# RecoveryBoard.net
KiCad netlist of a schematic drawn in EAGLE
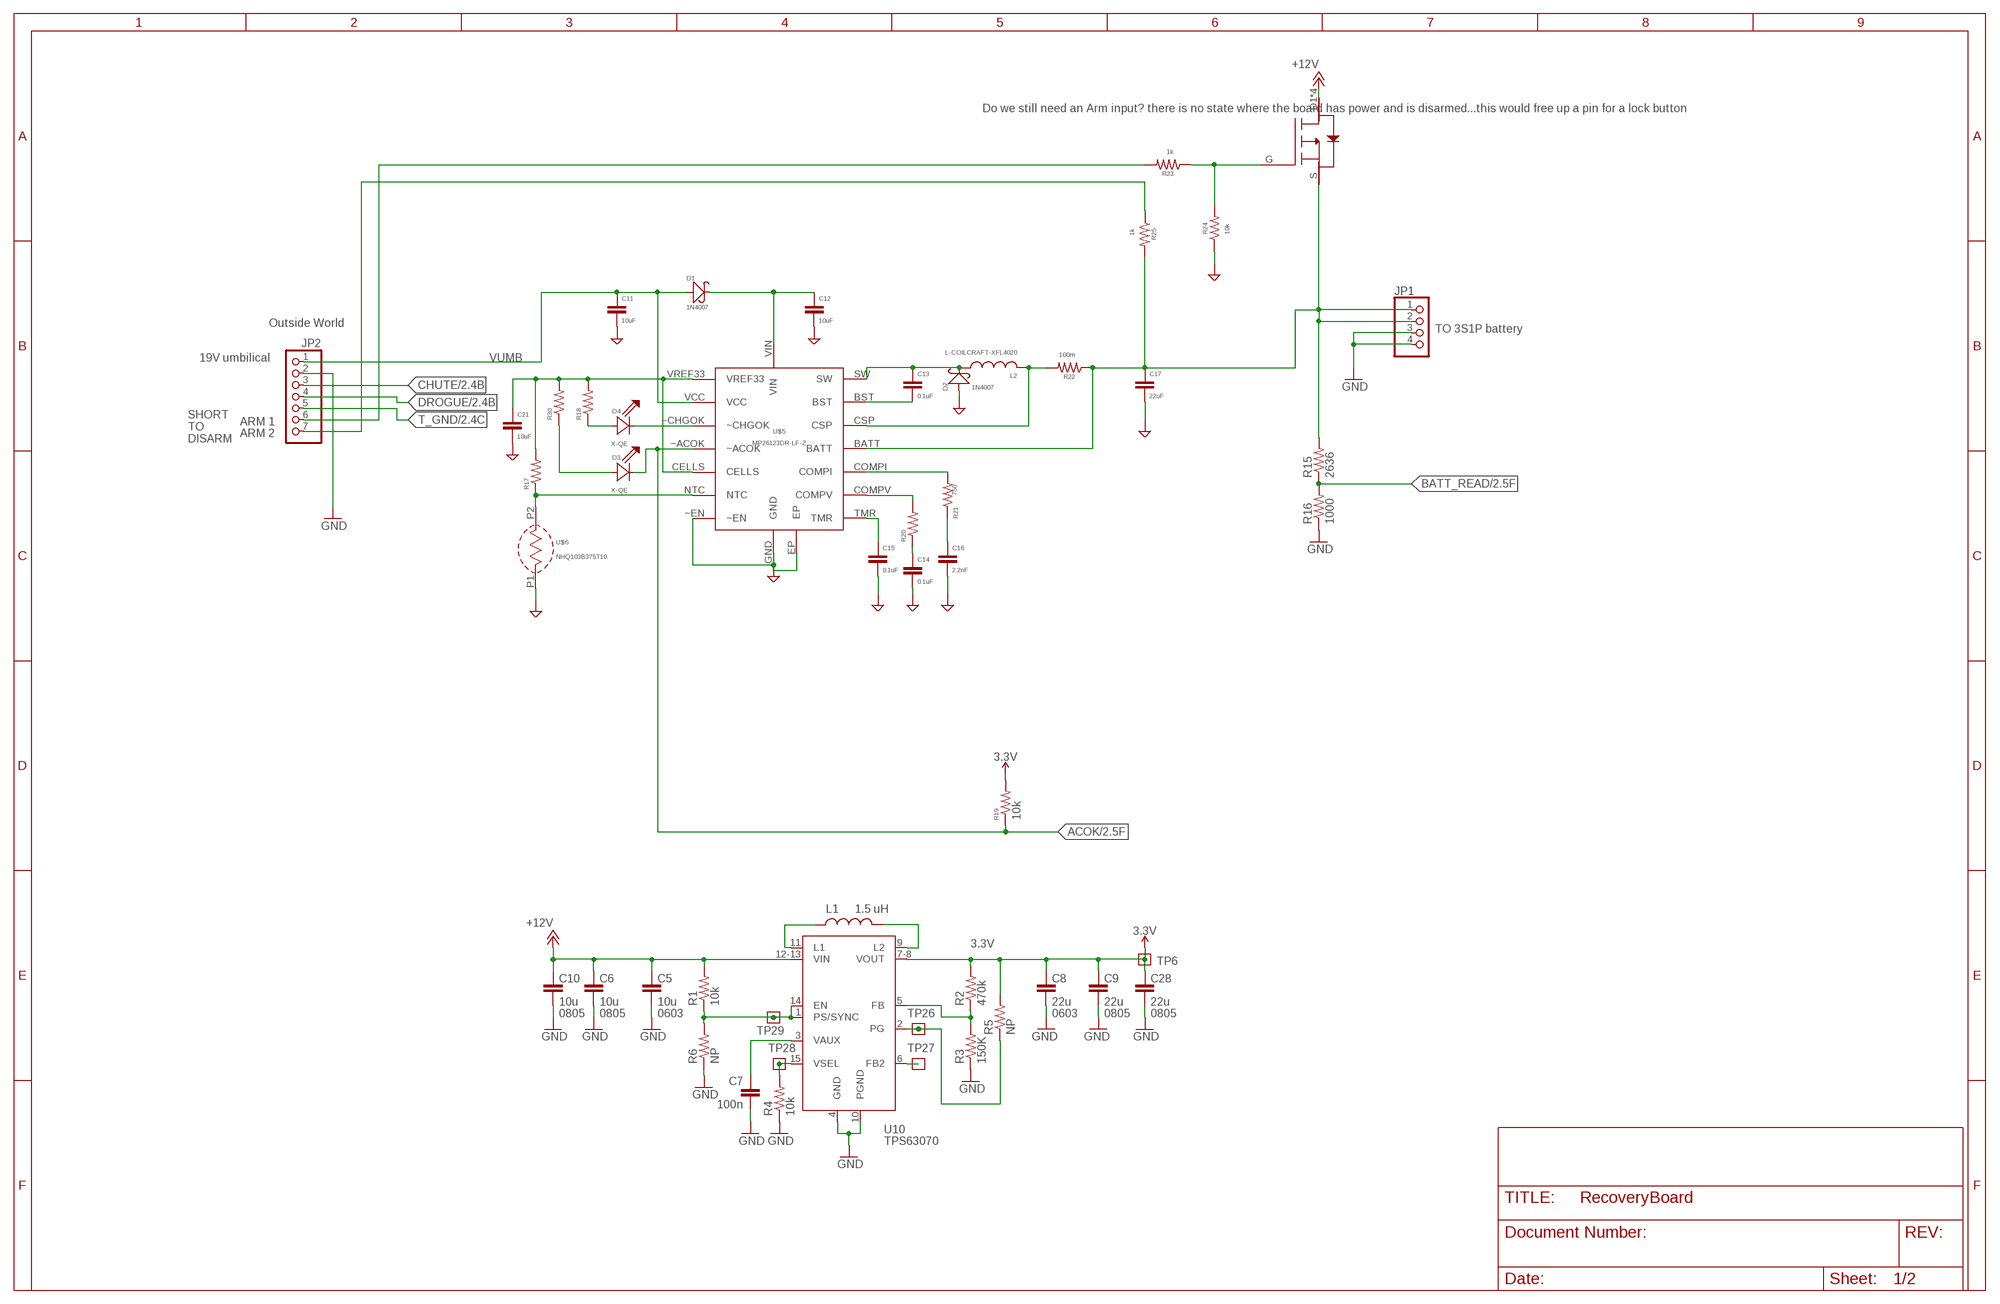
[diagram p0: schematic, sheet 1]
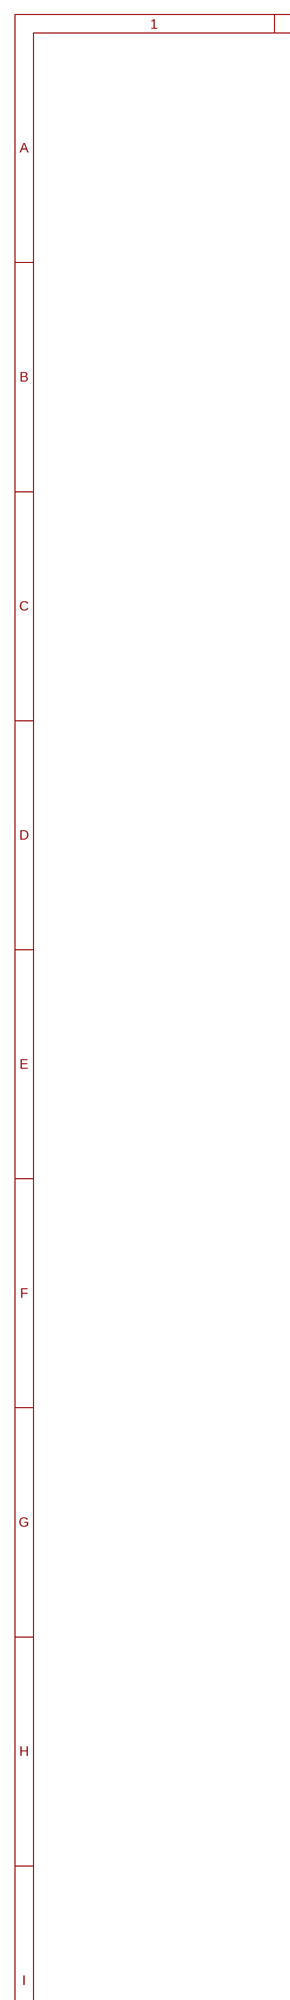
[diagram p1: schematic, sheet 2, part 1 of 2]
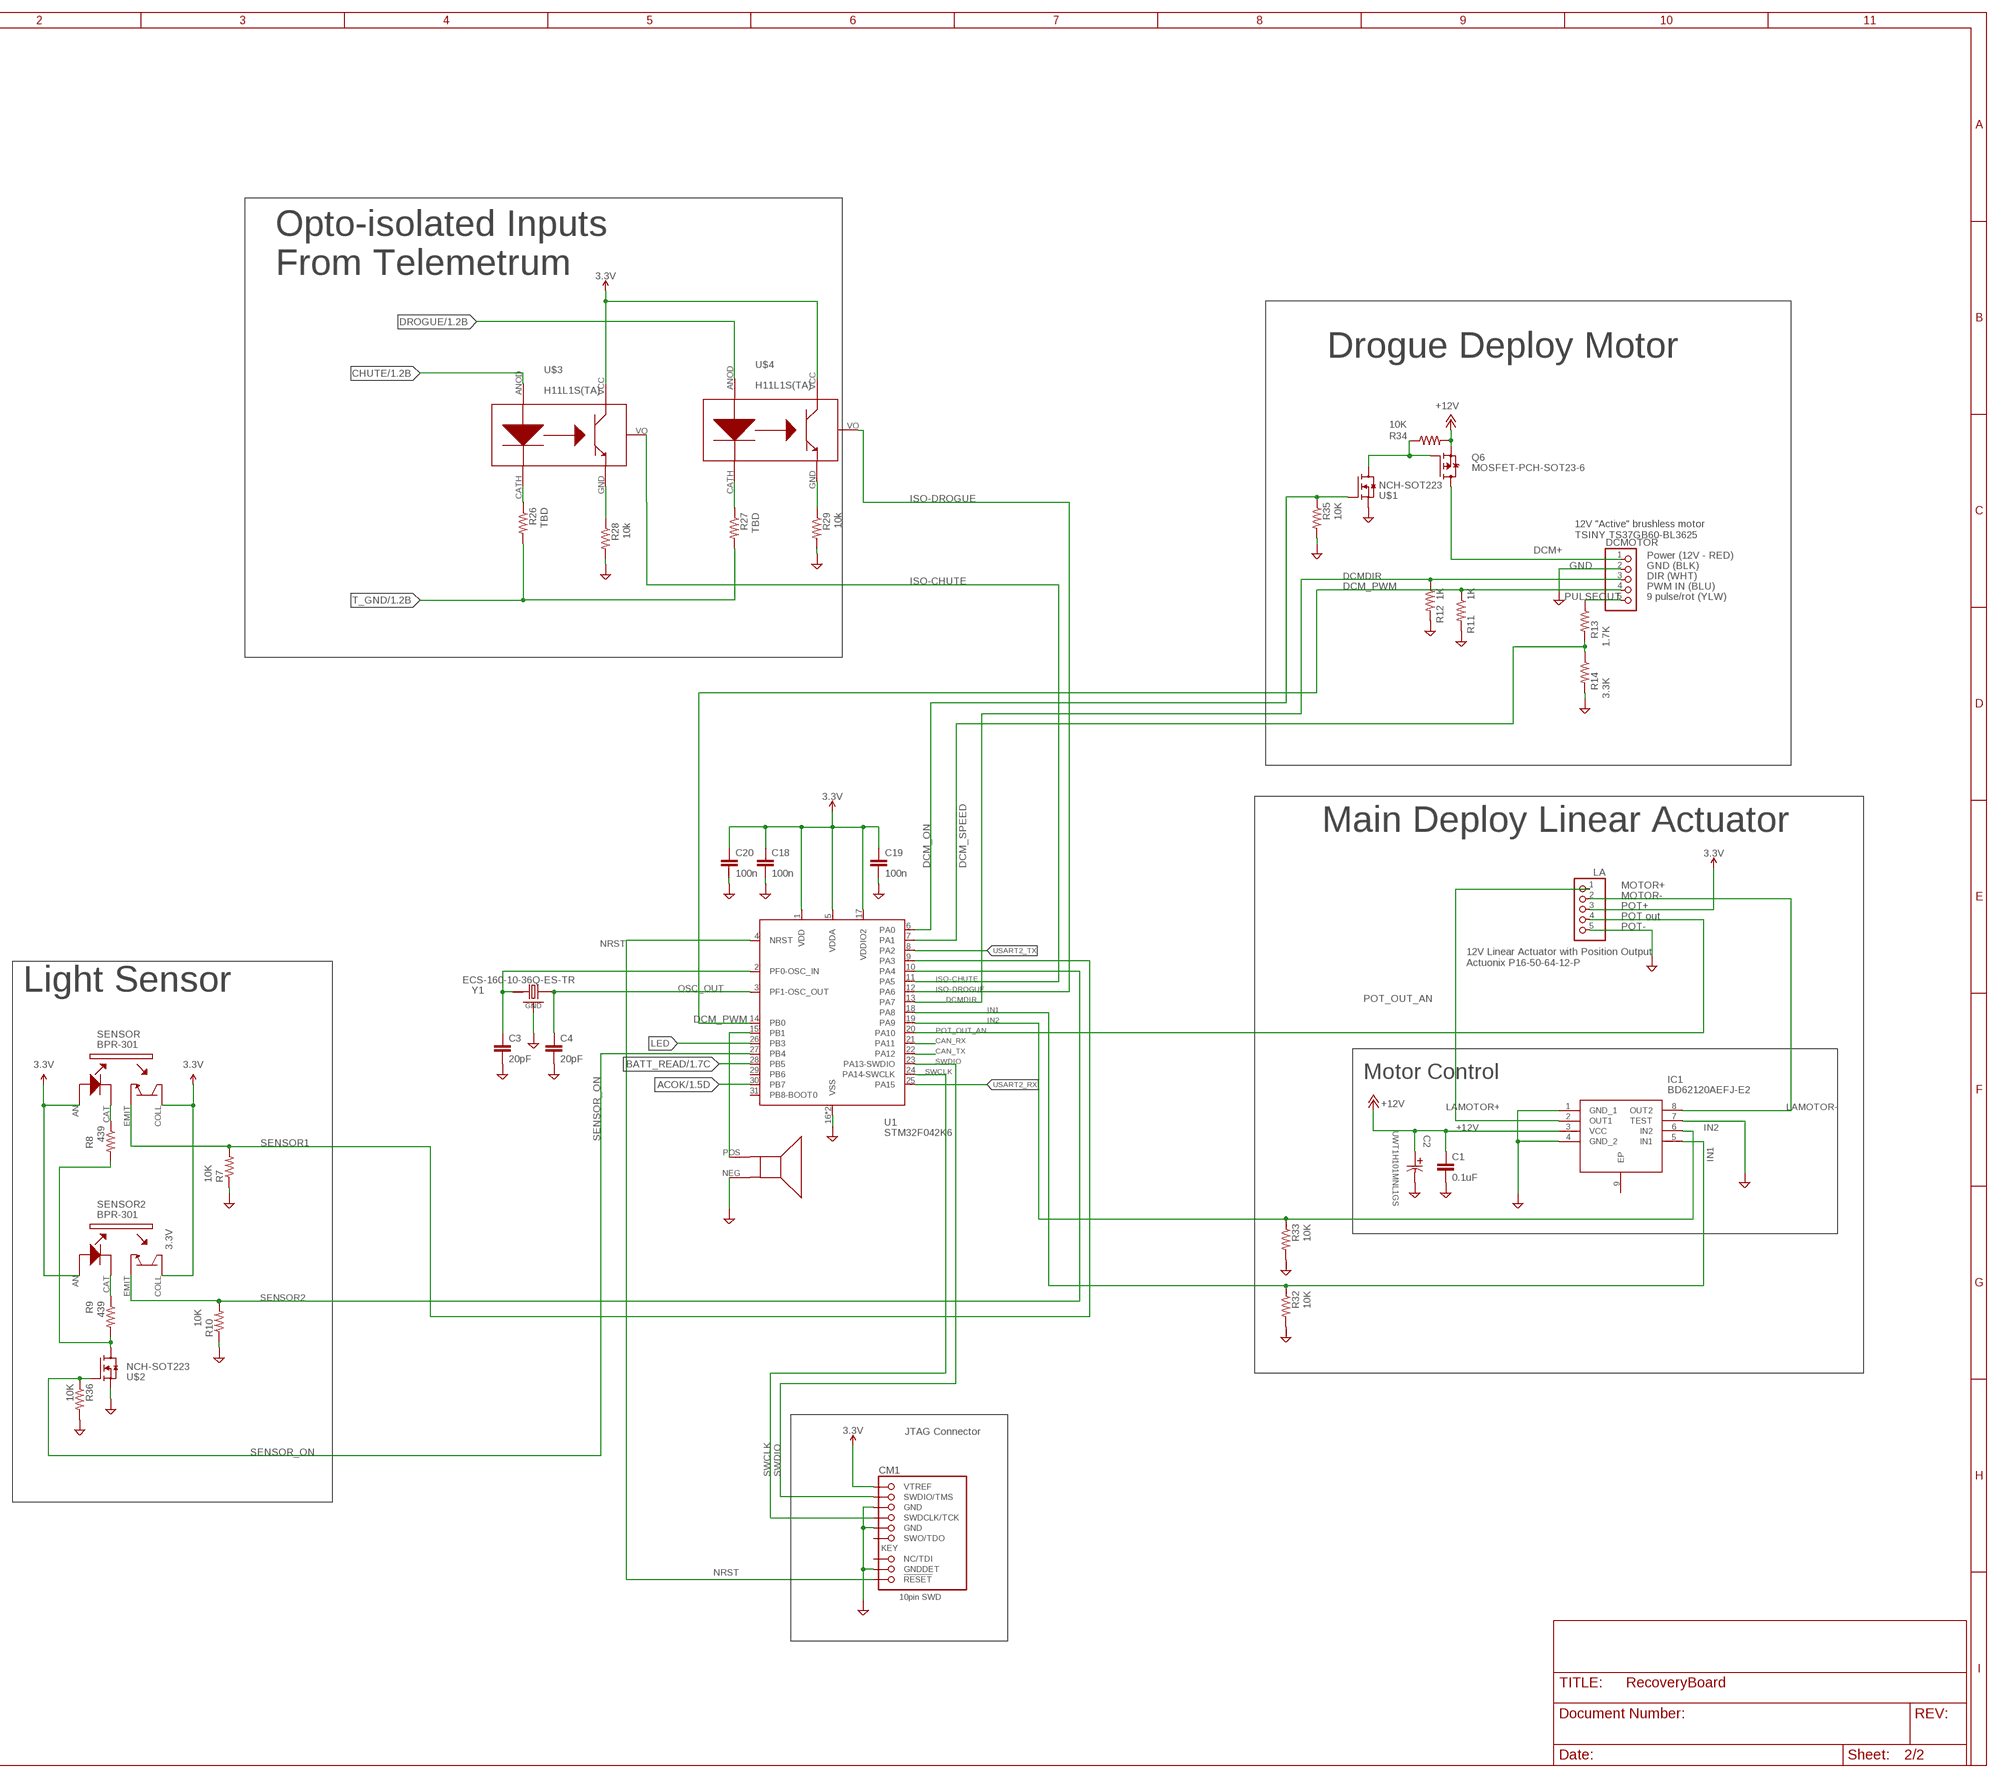
[diagram p2: schematic, sheet 2, part 2 of 2]

(export (version "E")
  (design (tool "Eeschema 10.0.6"))
  (components
    (comp (ref "C1")
      (value "0.1uF")
      (footprint "eagle-import:C0402")
      (libsource (lib "eagle-import") (part "rcl_334_C-EUC0402"))
    )
    (comp (ref "C2")
      (value "UWT1H101MNL1GS")
      (footprint "eagle-import:PCAP_8X10-ELECT")
      (libsource (lib "eagle-import") (part "UWT1H101MNL1GS"))
    )
    (comp (ref "C3")
      (value "20pF")
      (footprint "eagle-import:C0402")
      (libsource (lib "eagle-import") (part "rcl_334_C-EUC0402"))
    )
    (comp (ref "C4")
      (value "20pF")
      (footprint "eagle-import:C0402")
      (libsource (lib "eagle-import") (part "rcl_334_C-EUC0402"))
    )
    (comp (ref "C18")
      (value "100n")
      (footprint "eagle-import:C0402")
      (libsource (lib "eagle-import") (part "rcl_334_C-EUC0402"))
    )
    (comp (ref "C19")
      (value "100n")
      (footprint "eagle-import:C0402")
      (libsource (lib "eagle-import") (part "rcl_334_C-EUC0402"))
    )
    (comp (ref "C20")
      (value "100n")
      (footprint "eagle-import:C0402")
      (libsource (lib "eagle-import") (part "rcl_334_C-EUC0402"))
    )
    (comp (ref "CM1")
      (value "FTSH-105-XX-X-DV-K")
      (footprint "eagle-import:CON10_2X5_DUK_FTSH")
      (libsource (lib "eagle-import") (part "FTSH-105-XX-X-DV-K"))
    )
    (comp (ref "DCMOTOR")
      (value "PINHD-1X5")
      (footprint "eagle-import:1X05")
      (libsource (lib "eagle-import") (part "PINHD-1X5"))
    )
    (comp (ref "IC1")
      (value "BD62120AEFJ-E2")
      (footprint "eagle-import:SOIC127P600X100-9N")
      (fields (field (name "MOUSER_PART_NUMBER") "755-BD62120AEFJ-E2"))
      (libsource (lib "eagle-import") (part "BD62120AEFJ-E2"))
    )
    (comp (ref "LA")
      (value "PINHD-1X5")
      (footprint "eagle-import:1X05")
      (libsource (lib "eagle-import") (part "PINHD-1X5"))
    )
    (comp (ref "Q6")
      (value "MOSFET-PCH-SOT23-6")
      (footprint "eagle-import:SOT23-6")
      (libsource (lib "eagle-import") (part "MOSFET-PCH-SOT23-6"))
    )
    (comp (ref "R7")
      (value "10K")
      (footprint "eagle-import:R0402")
      (libsource (lib "eagle-import") (part "rcl_334_R-US_R0402"))
    )
    (comp (ref "R8")
      (value "439")
      (footprint "eagle-import:R0402")
      (libsource (lib "eagle-import") (part "rcl_334_R-US_R0402"))
    )
    (comp (ref "R9")
      (value "439")
      (footprint "eagle-import:R0402")
      (libsource (lib "eagle-import") (part "rcl_334_R-US_R0402"))
    )
    (comp (ref "R10")
      (value "10K")
      (footprint "eagle-import:R0402")
      (libsource (lib "eagle-import") (part "rcl_334_R-US_R0402"))
    )
    (comp (ref "R11")
      (value "1K")
      (footprint "eagle-import:R0402")
      (libsource (lib "eagle-import") (part "rcl_334_R-US_R0402"))
    )
    (comp (ref "R12")
      (value "1K")
      (footprint "eagle-import:R0402")
      (libsource (lib "eagle-import") (part "rcl_334_R-US_R0402"))
    )
    (comp (ref "R13")
      (value "1.7K")
      (footprint "eagle-import:R0402")
      (libsource (lib "eagle-import") (part "rcl_334_R-US_R0402"))
    )
    (comp (ref "R14")
      (value "3.3K")
      (footprint "eagle-import:R0402")
      (libsource (lib "eagle-import") (part "rcl_334_R-US_R0402"))
    )
    (comp (ref "R26")
      (value "TBD")
      (footprint "eagle-import:R0402")
      (libsource (lib "eagle-import") (part "rcl_334_R-US_R0402"))
    )
    (comp (ref "R27")
      (value "TBD")
      (footprint "eagle-import:R0402")
      (libsource (lib "eagle-import") (part "rcl_334_R-US_R0402"))
    )
    (comp (ref "R28")
      (value "10k")
      (footprint "eagle-import:R0402")
      (libsource (lib "eagle-import") (part "rcl_334_R-US_R0402"))
    )
    (comp (ref "R29")
      (value "10k")
      (footprint "eagle-import:R0402")
      (libsource (lib "eagle-import") (part "rcl_334_R-US_R0402"))
    )
    (comp (ref "R32")
      (value "10K")
      (footprint "eagle-import:R0402")
      (libsource (lib "eagle-import") (part "rcl_334_R-US_R0402"))
    )
    (comp (ref "R33")
      (value "10K")
      (footprint "eagle-import:R0402")
      (libsource (lib "eagle-import") (part "rcl_334_R-US_R0402"))
    )
    (comp (ref "R34")
      (value "10K")
      (footprint "eagle-import:R0402")
      (libsource (lib "eagle-import") (part "rcl_334_R-US_R0402"))
    )
    (comp (ref "R35")
      (value "10K")
      (footprint "eagle-import:R0402")
      (libsource (lib "eagle-import") (part "rcl_334_R-US_R0402"))
    )
    (comp (ref "R36")
      (value "10K")
      (footprint "eagle-import:R0402")
      (libsource (lib "eagle-import") (part "rcl_334_R-US_R0402"))
    )
    (comp (ref "SENSOR")
      (value "BPR-301")
      (footprint "eagle-import:BPR-301")
      (libsource (lib "eagle-import") (part "BPR-301"))
    )
    (comp (ref "SENSOR2")
      (value "BPR-301")
      (footprint "eagle-import:BPR-301")
      (libsource (lib "eagle-import") (part "BPR-301"))
    )
    (comp (ref "U$1")
      (value "NCH-SOT223")
      (footprint "eagle-import:SOT223")
      (libsource (lib "eagle-import") (part "NCH-SOT223"))
    )
    (comp (ref "U$2")
      (value "NCH-SOT223")
      (footprint "eagle-import:SOT223")
      (libsource (lib "eagle-import") (part "NCH-SOT223"))
    )
    (comp (ref "U$3")
      (value "H11L1S(TA)")
      (footprint "eagle-import:H11L1S(TA)")
      (libsource (lib "eagle-import") (part "H11L1S(TA)"))
    )
    (comp (ref "U$4")
      (value "H11L1S(TA)")
      (footprint "eagle-import:H11L1S(TA)")
      (libsource (lib "eagle-import") (part "H11L1S(TA)"))
    )
    (comp (ref "U$7")
      (value "SMT-0440-S-R")
      (footprint "eagle-import:SMT-0440-S-R")
      (libsource (lib "eagle-import") (part "SMT-0440-S-R"))
    )
    (comp (ref "U1")
      (value "STM32F042K6")
      (footprint "eagle-import:QFP32-7X7")
      (libsource (lib "eagle-import") (part "STM32F042K6"))
    )
    (comp (ref "Y1")
      (value "ECS-160-10-36Q-ES-TR")
      (footprint "eagle-import:XTAL_ECS-160-10-36Q-ES-TR")
      (fields (field (name "DIGI-KEY_PART_NUMBER") "XC2181CT-ND") (field (name "MF") "ECS Inc."))
      (libsource (lib "eagle-import") (part "ECS-160-10-36Q-ES-TR"))
    )
    (comp (ref "C5")
      (value "10u")
      (footprint "eagle-import:.0603-B-NOSILK")
      (fields (field (name "MFR") "Samsung") (field (name "MPN") "CL05B104KO5NNNC"))
      (libsource (lib "eagle-import") (part "C-EU0603-B-NOSILK"))
    )
    (comp (ref "C6")
      (value "10u")
      (footprint "eagle-import:.0805-B-NOSILK")
      (libsource (lib "eagle-import") (part "C-EU0805-B-NOSILK"))
    )
    (comp (ref "C7")
      (value "100n")
      (footprint "eagle-import:.0402-B-NOSILK")
      (fields (field (name "MFR") "Samsung") (field (name "MPN") "CL05B104KO5NNNC"))
      (libsource (lib "eagle-import") (part "rcl_custom_C-EU0402-B-NOSILK"))
    )
    (comp (ref "C8")
      (value "22u")
      (footprint "eagle-import:.0603-B-NOSILK")
      (fields (field (name "MFR") "Samsung") (field (name "MPN") "CL05B104KO5NNNC"))
      (libsource (lib "eagle-import") (part "C-EU0603-B-NOSILK"))
    )
    (comp (ref "C9")
      (value "22u")
      (footprint "eagle-import:.0805-B-NOSILK")
      (libsource (lib "eagle-import") (part "C-EU0805-B-NOSILK"))
    )
    (comp (ref "C10")
      (value "10u")
      (footprint "eagle-import:.0805-B-NOSILK")
      (libsource (lib "eagle-import") (part "C-EU0805-B-NOSILK"))
    )
    (comp (ref "C11")
      (value "10uF")
      (footprint "eagle-import:.0805-C-NOSILK")
      (libsource (lib "eagle-import") (part "C-EU0805-C-NOSILK"))
    )
    (comp (ref "C12")
      (value "10uF")
      (footprint "eagle-import:.0805-C-NOSILK")
      (libsource (lib "eagle-import") (part "C-EU0805-C-NOSILK"))
    )
    (comp (ref "C13")
      (value "0.1uF")
      (footprint "eagle-import:.0603-C-NOSILK")
      (libsource (lib "eagle-import") (part "C-EU0603-C-NOSILK"))
    )
    (comp (ref "C14")
      (value "0.1uF")
      (footprint "eagle-import:.0603-C-NOSILK")
      (libsource (lib "eagle-import") (part "C-EU0603-C-NOSILK"))
    )
    (comp (ref "C15")
      (value "0.1uF")
      (footprint "eagle-import:.0603-C-NOSILK")
      (libsource (lib "eagle-import") (part "C-EU0603-C-NOSILK"))
    )
    (comp (ref "C16")
      (value "2.2nF")
      (footprint "eagle-import:.0603-C-NOSILK")
      (libsource (lib "eagle-import") (part "C-EU0603-C-NOSILK"))
    )
    (comp (ref "C17")
      (value "22uF")
      (footprint "eagle-import:.0603-C-NOSILK")
      (libsource (lib "eagle-import") (part "C-EU0603-C-NOSILK"))
    )
    (comp (ref "C21")
      (value "10uF")
      (footprint "eagle-import:.0805-C-NOSILK")
      (libsource (lib "eagle-import") (part "C-EU0805-C-NOSILK"))
    )
    (comp (ref "C28")
      (value "22u")
      (footprint "eagle-import:.0805-B-NOSILK")
      (libsource (lib "eagle-import") (part "C-EU0805-B-NOSILK"))
    )
    (comp (ref "D1")
      (value "1N4007")
      (footprint "eagle-import:DO-214AC")
      (libsource (lib "eagle-import") (part "DIODE-SCHOTTKY-(DO-214AC)"))
    )
    (comp (ref "D2")
      (value "1N4007")
      (footprint "eagle-import:DO-214AC")
      (libsource (lib "eagle-import") (part "DIODE-SCHOTTKY-(DO-214AC)"))
    )
    (comp (ref "D3")
      (value "X-QE")
      (footprint "eagle-import:X-QE")
      (libsource (lib "eagle-import") (part "X-QE"))
    )
    (comp (ref "D4")
      (value "X-QE")
      (footprint "eagle-import:X-QE")
      (libsource (lib "eagle-import") (part "X-QE"))
    )
    (comp (ref "JP1")
      (value "PINHD-1X4")
      (footprint "eagle-import:1X04")
      (libsource (lib "eagle-import") (part "PINHD-1X4"))
    )
    (comp (ref "JP2")
      (value "PINHD-1X7")
      (footprint "eagle-import:1X07")
      (libsource (lib "eagle-import") (part "PINHD-1X7"))
    )
    (comp (ref "L1")
      (value "1.5 uH")
      (footprint "eagle-import:L-COILCRAFT-XFL4020")
      (fields (field (name "MFR") "Coilcraft") (field (name "MPN") "XFL4020-152ME"))
      (libsource (lib "eagle-import") (part "L-COILCRAFT-XFL4020"))
    )
    (comp (ref "L2")
      (value "L-COILCRAFT-XFL4020")
      (footprint "eagle-import:L-COILCRAFT-XFL4020")
      (libsource (lib "eagle-import") (part "L-COILCRAFT-XFL4020"))
    )
    (comp (ref "R1")
      (value "10k")
      (footprint "eagle-import:.0402-B-NOSILK")
      (fields (field (name "MFR") "Samsung") (field (name "MPN") "RC1005F6653CS"))
      (libsource (lib "eagle-import") (part "rcl_custom_R-US_0402-B-NOSILK"))
    )
    (comp (ref "R2")
      (value "470k")
      (footprint "eagle-import:.0402-B-NOSILK")
      (fields (field (name "MFR") "Samsung") (field (name "MPN") "RC1005F6653CS"))
      (libsource (lib "eagle-import") (part "rcl_custom_R-US_0402-B-NOSILK"))
    )
    (comp (ref "R3")
      (value "150K")
      (footprint "eagle-import:.0402-B-NOSILK")
      (fields (field (name "MFR") "Samsung") (field (name "MPN") "RC1005F6653CS"))
      (libsource (lib "eagle-import") (part "rcl_custom_R-US_0402-B-NOSILK"))
    )
    (comp (ref "R4")
      (value "10k")
      (footprint "eagle-import:.0402-B-NOSILK")
      (fields (field (name "MFR") "Samsung") (field (name "MPN") "RC1005F6653CS"))
      (libsource (lib "eagle-import") (part "rcl_custom_R-US_0402-B-NOSILK"))
    )
    (comp (ref "R5")
      (value "NP")
      (footprint "eagle-import:.0402-B-NOSILK")
      (fields (field (name "MFR") "Samsung") (field (name "MPN") "RC1005F6653CS"))
      (libsource (lib "eagle-import") (part "rcl_custom_R-US_0402-B-NOSILK"))
    )
    (comp (ref "R6")
      (value "NP")
      (footprint "eagle-import:.0402-B-NOSILK")
      (fields (field (name "MFR") "Samsung") (field (name "MPN") "RC1005F6653CS"))
      (libsource (lib "eagle-import") (part "rcl_custom_R-US_0402-B-NOSILK"))
    )
    (comp (ref "R15")
      (value "2636")
      (footprint "eagle-import:.0603-C-NOSILK")
      (fields (field (name "MFR") "Samsung") (field (name "MPN") "RC1005F6653CS"))
      (libsource (lib "eagle-import") (part "R-US_0603-C-NOSILK"))
    )
    (comp (ref "R16")
      (value "1000")
      (footprint "eagle-import:.0603-C-NOSILK")
      (fields (field (name "MFR") "Samsung") (field (name "MPN") "RC1005F6653CS"))
      (libsource (lib "eagle-import") (part "R-US_0603-C-NOSILK"))
    )
    (comp (ref "R17")
      (value "R-US_0603-C-NOSILK")
      (footprint "eagle-import:.0603-C-NOSILK")
      (libsource (lib "eagle-import") (part "R-US_0603-C-NOSILK"))
    )
    (comp (ref "R18")
      (value "R-US_0603-C-NOSILK")
      (footprint "eagle-import:.0603-C-NOSILK")
      (libsource (lib "eagle-import") (part "R-US_0603-C-NOSILK"))
    )
    (comp (ref "R19")
      (value "10k")
      (footprint "eagle-import:.0603-C-NOSILK")
      (libsource (lib "eagle-import") (part "R-US_0603-C-NOSILK"))
    )
    (comp (ref "R20")
      (value "R-US_0603-C-NOSILK")
      (footprint "eagle-import:.0603-C-NOSILK")
      (libsource (lib "eagle-import") (part "R-US_0603-C-NOSILK"))
    )
    (comp (ref "R21")
      (value "750")
      (footprint "eagle-import:.0603-C-NOSILK")
      (libsource (lib "eagle-import") (part "R-US_0603-C-NOSILK"))
    )
    (comp (ref "R22")
      (value "100m")
      (footprint "eagle-import:1206-C")
      (libsource (lib "eagle-import") (part "R-US_1206-C"))
    )
    (comp (ref "R23")
      (value "1k")
      (footprint "eagle-import:.0603-C-NOSILK")
      (libsource (lib "eagle-import") (part "R-US_0603-C-NOSILK"))
    )
    (comp (ref "R24")
      (value "10k")
      (footprint "eagle-import:.0603-C-NOSILK")
      (libsource (lib "eagle-import") (part "R-US_0603-C-NOSILK"))
    )
    (comp (ref "R25")
      (value "1k")
      (footprint "eagle-import:.0603-C-NOSILK")
      (libsource (lib "eagle-import") (part "R-US_0603-C-NOSILK"))
    )
    (comp (ref "R30")
      (value "R-US_0603-C-NOSILK")
      (footprint "eagle-import:.0603-C-NOSILK")
      (libsource (lib "eagle-import") (part "R-US_0603-C-NOSILK"))
    )
    (comp (ref "TP6")
      (value "TEST-POINT")
      (footprint "eagle-import:2MM-TEST-POINT")
      (libsource (lib "eagle-import") (part "TEST-POINT"))
    )
    (comp (ref "TP26")
      (value "TEST-POINT")
      (footprint "eagle-import:2MM-TEST-POINT")
      (libsource (lib "eagle-import") (part "TEST-POINT"))
    )
    (comp (ref "TP27")
      (value "TEST-POINT")
      (footprint "eagle-import:2MM-TEST-POINT")
      (libsource (lib "eagle-import") (part "TEST-POINT"))
    )
    (comp (ref "TP28")
      (value "TEST-POINT")
      (footprint "eagle-import:2MM-TEST-POINT")
      (libsource (lib "eagle-import") (part "TEST-POINT"))
    )
    (comp (ref "TP29")
      (value "TEST-POINT")
      (footprint "eagle-import:2MM-TEST-POINT")
      (libsource (lib "eagle-import") (part "TEST-POINT"))
    )
    (comp (ref "U$5")
      (value "MP26123DR-LF-Z")
      (footprint "eagle-import:MP26123DR-LF-Z")
      (libsource (lib "eagle-import") (part "MP26123DR-LF-Z"))
    )
    (comp (ref "U$6")
      (value "NHQ103B375T10")
      (footprint "eagle-import:NHQ103B375T10")
      (libsource (lib "eagle-import") (part "NHQ103B375T10"))
    )
    (comp (ref "U$8")
      (value "AO6405")
      (footprint "eagle-import:AO6405")
      (libsource (lib "eagle-import") (part "AO6405"))
    )
    (comp (ref "U10")
      (value "TPS63070")
      (footprint "eagle-import:TPS63070X")
      (libsource (lib "eagle-import") (part "TPS63070X"))
    )
  )
  (nets
    (net (code "1") (name "+12V") (class "Default")
      (node (ref "C1") (pin "1") (pinfunction "1_1") (pintype "passive"))
      (node (ref "C10") (pin "1") (pinfunction "1_1") (pintype "passive"))
      (node (ref "C2") (pin "1") (pinfunction "1_1") (pintype "passive"))
      (node (ref "C5") (pin "1") (pinfunction "1_1") (pintype "passive"))
      (node (ref "C6") (pin "1") (pinfunction "1_1") (pintype "passive"))
      (node (ref "IC1") (pin "3") (pinfunction "VCC_3") (pintype "bidirectional"))
      (node (ref "Q6") (pin "4") (pinfunction "S_4") (pintype "passive"))
      (node (ref "R1") (pin "2") (pinfunction "2_2") (pintype "passive"))
      (node (ref "R34") (pin "2") (pinfunction "2_2") (pintype "passive"))
      (node (ref "U$8") (pin "D1") (pinfunction "D_D1") (pintype "bidirectional"))
      (node (ref "U$8") (pin "D2") (pinfunction "D_D2") (pintype "bidirectional"))
      (node (ref "U$8") (pin "D3") (pinfunction "D_D3") (pintype "bidirectional"))
      (node (ref "U$8") (pin "D4") (pinfunction "D_D4") (pintype "bidirectional"))
      (node (ref "U10") (pin "12-13") (pinfunction "VIN_12-13") (pintype "power_in"))
    )
    (net (code "2") (name "3.3V") (class "Default")
      (node (ref "C18") (pin "1") (pinfunction "1_1") (pintype "passive"))
      (node (ref "C19") (pin "1") (pinfunction "1_1") (pintype "passive"))
      (node (ref "C20") (pin "1") (pinfunction "1_1") (pintype "passive"))
      (node (ref "C28") (pin "1") (pinfunction "1_1") (pintype "passive"))
      (node (ref "C8") (pin "1") (pinfunction "1_1") (pintype "passive"))
      (node (ref "C9") (pin "1") (pinfunction "1_1") (pintype "passive"))
      (node (ref "CM1") (pin "1") (pinfunction "VTREF_1") (pintype "passive"))
      (node (ref "LA") (pin "3") (pinfunction "3_3") (pintype "passive"))
      (node (ref "R19") (pin "2") (pinfunction "2_2") (pintype "passive"))
      (node (ref "R2") (pin "2") (pinfunction "2_2") (pintype "passive"))
      (node (ref "R5") (pin "2") (pinfunction "2_2") (pintype "passive"))
      (node (ref "SENSOR") (pin "AN") (pinfunction "ANOD_AN") (pintype "bidirectional"))
      (node (ref "SENSOR") (pin "COLL") (pinfunction "COLL_COLL") (pintype "bidirectional"))
      (node (ref "SENSOR2") (pin "AN") (pinfunction "ANOD_AN") (pintype "bidirectional"))
      (node (ref "SENSOR2") (pin "COLL") (pinfunction "COLL_COLL") (pintype "bidirectional"))
      (node (ref "TP6") (pin "1") (pinfunction "1_1") (pintype "passive"))
      (node (ref "U$3") (pin "VCC") (pinfunction "COLL_VCC") (pintype "bidirectional"))
      (node (ref "U$4") (pin "VCC") (pinfunction "COLL_VCC") (pintype "bidirectional"))
      (node (ref "U1") (pin "1") (pinfunction "VDD_1") (pintype "power_in"))
      (node (ref "U1") (pin "17") (pinfunction "VDDIO2_17") (pintype "power_in"))
      (node (ref "U1") (pin "5") (pinfunction "VDDA_5") (pintype "power_in"))
      (node (ref "U10") (pin "7-8") (pinfunction "VOUT_7-8") (pintype "power_in"))
    )
    (net (code "3") (name "ACOK") (class "Default")
      (node (ref "D3") (pin "CATHODE") (pinfunction "C_CATHODE") (pintype "passive"))
      (node (ref "R19") (pin "1") (pinfunction "1_1") (pintype "passive"))
      (node (ref "U$5") (pin "~ACOK") (pinfunction "~{ACOK}_~ACOK") (pintype "bidirectional"))
      (node (ref "U1") (pin "30") (pinfunction "PB7_30") (pintype "bidirectional"))
    )
    (net (code "4") (name "BATT_READ") (class "Default")
      (node (ref "R15") (pin "1") (pinfunction "1_1") (pintype "passive"))
      (node (ref "R16") (pin "2") (pinfunction "2_2") (pintype "passive"))
      (node (ref "U1") (pin "28") (pinfunction "PB5_28") (pintype "bidirectional"))
    )
    (net (code "5") (name "CAN_RX") (class "Default")
      (node (ref "U1") (pin "21") (pinfunction "PA11_21") (pintype "bidirectional"))
    )
    (net (code "6") (name "CAN_TX") (class "Default")
      (node (ref "U1") (pin "22") (pinfunction "PA12_22") (pintype "bidirectional"))
    )
    (net (code "7") (name "CHUTE") (class "Default")
      (node (ref "JP2") (pin "3") (pinfunction "3_3") (pintype "passive"))
      (node (ref "U$3") (pin "ANOD") (pinfunction "ANOD_ANOD") (pintype "bidirectional"))
    )
    (net (code "8") (name "DCM+") (class "Default")
      (node (ref "DCMOTOR") (pin "1") (pinfunction "1_1") (pintype "passive"))
      (node (ref "Q6") (pin "1") (pinfunction "D_1") (pintype "passive"))
      (node (ref "Q6") (pin "2") (pinfunction "D_2") (pintype "passive"))
      (node (ref "Q6") (pin "5") (pinfunction "D_5") (pintype "passive"))
      (node (ref "Q6") (pin "6") (pinfunction "D_6") (pintype "passive"))
    )
    (net (code "9") (name "DCMDIR") (class "Default")
      (node (ref "DCMOTOR") (pin "3") (pinfunction "3_3") (pintype "passive"))
      (node (ref "R12") (pin "1") (pinfunction "1_1") (pintype "passive"))
      (node (ref "U1") (pin "13") (pinfunction "PA7_13") (pintype "bidirectional"))
    )
    (net (code "10") (name "DCM_ON") (class "Default")
      (node (ref "R35") (pin "1") (pinfunction "1_1") (pintype "passive"))
      (node (ref "U$1") (pin "1") (pinfunction "G_1") (pintype "passive"))
      (node (ref "U1") (pin "6") (pinfunction "PA0_6") (pintype "bidirectional"))
    )
    (net (code "11") (name "DCM_PWM") (class "Default")
      (node (ref "DCMOTOR") (pin "4") (pinfunction "4_4") (pintype "passive"))
      (node (ref "R11") (pin "1") (pinfunction "1_1") (pintype "passive"))
      (node (ref "U1") (pin "14") (pinfunction "PB0_14") (pintype "bidirectional"))
    )
    (net (code "12") (name "DCM_SPEED") (class "Default")
      (node (ref "R13") (pin "2") (pinfunction "2_2") (pintype "passive"))
      (node (ref "R14") (pin "1") (pinfunction "1_1") (pintype "passive"))
      (node (ref "U1") (pin "7") (pinfunction "PA1_7") (pintype "bidirectional"))
    )
    (net (code "13") (name "DROGUE") (class "Default")
      (node (ref "JP2") (pin "4") (pinfunction "4_4") (pintype "passive"))
      (node (ref "U$4") (pin "ANOD") (pinfunction "ANOD_ANOD") (pintype "bidirectional"))
    )
    (net (code "14") (name "GND") (class "Default")
      (node (ref "C1") (pin "2") (pinfunction "2_2") (pintype "passive"))
      (node (ref "C10") (pin "2") (pinfunction "2_2") (pintype "passive"))
      (node (ref "C11") (pin "2") (pinfunction "2_2") (pintype "passive"))
      (node (ref "C12") (pin "2") (pinfunction "2_2") (pintype "passive"))
      (node (ref "C14") (pin "2") (pinfunction "2_2") (pintype "passive"))
      (node (ref "C15") (pin "2") (pinfunction "2_2") (pintype "passive"))
      (node (ref "C16") (pin "2") (pinfunction "2_2") (pintype "passive"))
      (node (ref "C17") (pin "2") (pinfunction "2_2") (pintype "passive"))
      (node (ref "C18") (pin "2") (pinfunction "2_2") (pintype "passive"))
      (node (ref "C19") (pin "2") (pinfunction "2_2") (pintype "passive"))
      (node (ref "C2") (pin "2") (pinfunction "2_2") (pintype "passive"))
      (node (ref "C20") (pin "2") (pinfunction "2_2") (pintype "passive"))
      (node (ref "C21") (pin "2") (pinfunction "2_2") (pintype "passive"))
      (node (ref "C28") (pin "2") (pinfunction "2_2") (pintype "passive"))
      (node (ref "C3") (pin "2") (pinfunction "2_2") (pintype "passive"))
      (node (ref "C4") (pin "2") (pinfunction "2_2") (pintype "passive"))
      (node (ref "C5") (pin "2") (pinfunction "2_2") (pintype "passive"))
      (node (ref "C6") (pin "2") (pinfunction "2_2") (pintype "passive"))
      (node (ref "C7") (pin "2") (pinfunction "2_2") (pintype "passive"))
      (node (ref "C8") (pin "2") (pinfunction "2_2") (pintype "passive"))
      (node (ref "C9") (pin "2") (pinfunction "2_2") (pintype "passive"))
      (node (ref "CM1") (pin "3") (pinfunction "GND_3") (pintype "passive"))
      (node (ref "CM1") (pin "5") (pinfunction "GND_5") (pintype "passive"))
      (node (ref "CM1") (pin "9") (pinfunction "GNDDET_9") (pintype "passive"))
      (node (ref "D2") (pin "1") (pinfunction "+_1") (pintype "passive"))
      (node (ref "DCMOTOR") (pin "2") (pinfunction "2_2") (pintype "passive"))
      (node (ref "IC1") (pin "1") (pinfunction "GND_1_1") (pintype "bidirectional"))
      (node (ref "IC1") (pin "4") (pinfunction "GND_2_4") (pintype "bidirectional"))
      (node (ref "IC1") (pin "7") (pinfunction "TEST_7") (pintype "bidirectional"))
      (node (ref "JP1") (pin "3") (pinfunction "3_3") (pintype "passive"))
      (node (ref "JP1") (pin "4") (pinfunction "4_4") (pintype "passive"))
      (node (ref "JP2") (pin "2") (pinfunction "2_2") (pintype "passive"))
      (node (ref "LA") (pin "5") (pinfunction "5_5") (pintype "passive"))
      (node (ref "R10") (pin "1") (pinfunction "1_1") (pintype "passive"))
      (node (ref "R11") (pin "2") (pinfunction "2_2") (pintype "passive"))
      (node (ref "R12") (pin "2") (pinfunction "2_2") (pintype "passive"))
      (node (ref "R14") (pin "2") (pinfunction "2_2") (pintype "passive"))
      (node (ref "R16") (pin "1") (pinfunction "1_1") (pintype "passive"))
      (node (ref "R24") (pin "1") (pinfunction "1_1") (pintype "passive"))
      (node (ref "R28") (pin "2") (pinfunction "2_2") (pintype "passive"))
      (node (ref "R29") (pin "2") (pinfunction "2_2") (pintype "passive"))
      (node (ref "R3") (pin "1") (pinfunction "1_1") (pintype "passive"))
      (node (ref "R32") (pin "2") (pinfunction "2_2") (pintype "passive"))
      (node (ref "R33") (pin "2") (pinfunction "2_2") (pintype "passive"))
      (node (ref "R35") (pin "2") (pinfunction "2_2") (pintype "passive"))
      (node (ref "R36") (pin "2") (pinfunction "2_2") (pintype "passive"))
      (node (ref "R4") (pin "1") (pinfunction "1_1") (pintype "passive"))
      (node (ref "R6") (pin "1") (pinfunction "1_1") (pintype "passive"))
      (node (ref "R7") (pin "1") (pinfunction "1_1") (pintype "passive"))
      (node (ref "U$1") (pin "3") (pinfunction "S_3") (pintype "passive"))
      (node (ref "U$2") (pin "3") (pinfunction "S_3") (pintype "passive"))
      (node (ref "U$5") (pin "EP") (pinfunction "EP_EP") (pintype "bidirectional"))
      (node (ref "U$5") (pin "GND") (pinfunction "GND_GND") (pintype "bidirectional"))
      (node (ref "U$5") (pin "~EN") (pinfunction "~{EN}_~EN") (pintype "bidirectional"))
      (node (ref "U$6") (pin "P1") (pinfunction "P1_P1") (pintype "bidirectional"))
      (node (ref "U$7") (pin "NEG") (pinfunction "NEG_NEG") (pintype "bidirectional"))
      (node (ref "U1") (pin "16") (pinfunction "VSS_16") (pintype "power_in"))
      (node (ref "U1") (pin "32") (pinfunction "VSS_32") (pintype "power_in"))
      (node (ref "U10") (pin "10") (pinfunction "PGND_10") (pintype "power_in"))
      (node (ref "U10") (pin "4") (pinfunction "GND_4") (pintype "power_in"))
      (node (ref "Y1") (pin "GND") (pinfunction "GND_GND") (pintype "power_in"))
      (node (ref "Y1") (pin "GND2") (pinfunction "GND_GND2") (pintype "power_in"))
    )
    (net (code "15") (name "IN1") (class "Default")
      (node (ref "IC1") (pin "5") (pinfunction "IN1_5") (pintype "bidirectional"))
      (node (ref "R32") (pin "1") (pinfunction "1_1") (pintype "passive"))
      (node (ref "U1") (pin "18") (pinfunction "PA8_18") (pintype "bidirectional"))
    )
    (net (code "16") (name "IN2") (class "Default")
      (node (ref "IC1") (pin "6") (pinfunction "IN2_6") (pintype "bidirectional"))
      (node (ref "R33") (pin "1") (pinfunction "1_1") (pintype "passive"))
      (node (ref "U1") (pin "19") (pinfunction "PA9_19") (pintype "bidirectional"))
    )
    (net (code "17") (name "ISO-CHUTE") (class "Default")
      (node (ref "U$3") (pin "VO") (pinfunction "OUTPUT_VO") (pintype "bidirectional"))
      (node (ref "U1") (pin "11") (pinfunction "PA5_11") (pintype "bidirectional"))
    )
    (net (code "18") (name "ISO-DROGUE") (class "Default")
      (node (ref "U$4") (pin "VO") (pinfunction "OUTPUT_VO") (pintype "bidirectional"))
      (node (ref "U1") (pin "12") (pinfunction "PA6_12") (pintype "bidirectional"))
    )
    (net (code "19") (name "LAMOTOR+") (class "Default")
      (node (ref "IC1") (pin "2") (pinfunction "OUT1_2") (pintype "bidirectional"))
      (node (ref "LA") (pin "1") (pinfunction "1_1") (pintype "passive"))
    )
    (net (code "20") (name "LAMOTOR-") (class "Default")
      (node (ref "IC1") (pin "8") (pinfunction "OUT2_8") (pintype "bidirectional"))
      (node (ref "LA") (pin "2") (pinfunction "2_2") (pintype "passive"))
    )
    (net (code "21") (name "LED") (class "Default")
      (node (ref "U1") (pin "26") (pinfunction "PB3_26") (pintype "bidirectional"))
    )
    (net (code "22") (name "NRST") (class "Default")
      (node (ref "CM1") (pin "10") (pinfunction "~{RESET}_10") (pintype "passive"))
      (node (ref "U1") (pin "4") (pinfunction "NRST_4") (pintype "bidirectional"))
    )
    (net (code "23") (name "Net-(C13-Pad2)") (class "Default")
      (node (ref "C13") (pin "2") (pinfunction "2_2") (pintype "passive"))
      (node (ref "U$5") (pin "BST") (pinfunction "BST_BST") (pintype "bidirectional"))
    )
    (net (code "24") (name "Net-(C14-Pad1)") (class "Default")
      (node (ref "C14") (pin "1") (pinfunction "1_1") (pintype "passive"))
      (node (ref "R20") (pin "1") (pinfunction "1_1") (pintype "passive"))
    )
    (net (code "25") (name "Net-(C15-Pad1)") (class "Default")
      (node (ref "C15") (pin "1") (pinfunction "1_1") (pintype "passive"))
      (node (ref "U$5") (pin "TMR") (pinfunction "TMR_TMR") (pintype "bidirectional"))
    )
    (net (code "26") (name "Net-(C16-Pad1)") (class "Default")
      (node (ref "C16") (pin "1") (pinfunction "1_1") (pintype "passive"))
      (node (ref "R21") (pin "1") (pinfunction "1_1") (pintype "passive"))
    )
    (net (code "27") (name "Net-(C17-Pad1)") (class "Default")
      (node (ref "C17") (pin "1") (pinfunction "1_1") (pintype "passive"))
      (node (ref "JP1") (pin "1") (pinfunction "1_1") (pintype "passive"))
      (node (ref "JP1") (pin "2") (pinfunction "2_2") (pintype "passive"))
      (node (ref "R15") (pin "2") (pinfunction "2_2") (pintype "passive"))
      (node (ref "R22") (pin "1") (pinfunction "1_1") (pintype "passive"))
      (node (ref "R25") (pin "2") (pinfunction "2_2") (pintype "passive"))
      (node (ref "U$5") (pin "BATT") (pinfunction "BATT_BATT") (pintype "bidirectional"))
      (node (ref "U$8") (pin "S") (pinfunction "S_S") (pintype "bidirectional"))
    )
    (net (code "28") (name "Net-(C21-Pad1)") (class "Default")
      (node (ref "C21") (pin "1") (pinfunction "1_1") (pintype "passive"))
      (node (ref "R17") (pin "2") (pinfunction "2_2") (pintype "passive"))
      (node (ref "R18") (pin "2") (pinfunction "2_2") (pintype "passive"))
      (node (ref "R30") (pin "2") (pinfunction "2_2") (pintype "passive"))
      (node (ref "U$5") (pin "CELLS") (pinfunction "CELLS_CELLS") (pintype "bidirectional"))
      (node (ref "U$5") (pin "VREF33") (pinfunction "VREF33_VREF33") (pintype "bidirectional"))
    )
    (net (code "29") (name "Net-(D1--)") (class "Default")
      (node (ref "C12") (pin "1") (pinfunction "1_1") (pintype "passive"))
      (node (ref "D1") (pin "2") (pinfunction "-_2") (pintype "passive"))
      (node (ref "U$5") (pin "VIN") (pinfunction "VIN_VIN") (pintype "bidirectional"))
    )
    (net (code "30") (name "Net-(D2--)") (class "Default")
      (node (ref "C13") (pin "1") (pinfunction "1_1") (pintype "passive"))
      (node (ref "D2") (pin "2") (pinfunction "-_2") (pintype "passive"))
      (node (ref "L2") (pin "1") (pinfunction "1_1") (pintype "passive"))
      (node (ref "U$5") (pin "SW") (pinfunction "SW_SW") (pintype "bidirectional"))
    )
    (net (code "31") (name "Net-(D3-A)") (class "Default")
      (node (ref "D3") (pin "ANODE") (pinfunction "A_ANODE") (pintype "passive"))
      (node (ref "R30") (pin "1") (pinfunction "1_1") (pintype "passive"))
    )
    (net (code "32") (name "Net-(D4-A)") (class "Default")
      (node (ref "D4") (pin "ANODE") (pinfunction "A_ANODE") (pintype "passive"))
      (node (ref "R18") (pin "1") (pinfunction "1_1") (pintype "passive"))
    )
    (net (code "33") (name "Net-(D4-C)") (class "Default")
      (node (ref "D4") (pin "CATHODE") (pinfunction "C_CATHODE") (pintype "passive"))
      (node (ref "U$5") (pin "~CHGOK") (pinfunction "~{CHGOK}_~CHGOK") (pintype "bidirectional"))
    )
    (net (code "34") (name "Net-(JP2-Pad6)") (class "Default")
      (node (ref "JP2") (pin "6") (pinfunction "6_6") (pintype "passive"))
      (node (ref "R23") (pin "2") (pinfunction "2_2") (pintype "passive"))
    )
    (net (code "35") (name "Net-(JP2-Pad7)") (class "Default")
      (node (ref "JP2") (pin "7") (pinfunction "7_7") (pintype "passive"))
      (node (ref "R25") (pin "1") (pinfunction "1_1") (pintype "passive"))
    )
    (net (code "36") (name "Net-(L2-Pad2)") (class "Default")
      (node (ref "L2") (pin "2") (pinfunction "2_2") (pintype "passive"))
      (node (ref "R22") (pin "2") (pinfunction "2_2") (pintype "passive"))
      (node (ref "U$5") (pin "CSP") (pinfunction "CSP_CSP") (pintype "bidirectional"))
    )
    (net (code "37") (name "Net-(Q6-G)") (class "Default")
      (node (ref "Q6") (pin "3") (pinfunction "G_3") (pintype "passive"))
      (node (ref "R34") (pin "1") (pinfunction "1_1") (pintype "passive"))
      (node (ref "U$1") (pin "2") (pinfunction "D_2") (pintype "passive"))
      (node (ref "U$1") (pin "4") (pinfunction "D_4") (pintype "passive"))
    )
    (net (code "38") (name "Net-(R8-Pad2)") (class "Default")
      (node (ref "R8") (pin "2") (pinfunction "2_2") (pintype "passive"))
      (node (ref "R9") (pin "2") (pinfunction "2_2") (pintype "passive"))
      (node (ref "U$2") (pin "2") (pinfunction "D_2") (pintype "passive"))
      (node (ref "U$2") (pin "4") (pinfunction "D_4") (pintype "passive"))
    )
    (net (code "39") (name "Net-(R17-Pad1)") (class "Default")
      (node (ref "R17") (pin "1") (pinfunction "1_1") (pintype "passive"))
      (node (ref "U$5") (pin "NTC") (pinfunction "NTC_NTC") (pintype "bidirectional"))
      (node (ref "U$6") (pin "P2") (pinfunction "P2_P2") (pintype "bidirectional"))
    )
    (net (code "40") (name "Net-(R20-Pad2)") (class "Default")
      (node (ref "R20") (pin "2") (pinfunction "2_2") (pintype "passive"))
      (node (ref "U$5") (pin "COMPV") (pinfunction "COMPV_COMPV") (pintype "bidirectional"))
    )
    (net (code "41") (name "Net-(R21-Pad2)") (class "Default")
      (node (ref "R21") (pin "2") (pinfunction "2_2") (pintype "passive"))
      (node (ref "U$5") (pin "COMPI") (pinfunction "COMPI_COMPI") (pintype "bidirectional"))
    )
    (net (code "42") (name "Net-(R23-Pad1)") (class "Default")
      (node (ref "R23") (pin "1") (pinfunction "1_1") (pintype "passive"))
      (node (ref "R24") (pin "2") (pinfunction "2_2") (pintype "passive"))
      (node (ref "U$8") (pin "G") (pinfunction "G_G") (pintype "bidirectional"))
    )
    (net (code "43") (name "Net-(SENSOR-CATH)") (class "Default")
      (node (ref "R8") (pin "1") (pinfunction "1_1") (pintype "passive"))
      (node (ref "SENSOR") (pin "CAT") (pinfunction "CATH_CAT") (pintype "bidirectional"))
    )
    (net (code "44") (name "Net-(SENSOR2-CATH)") (class "Default")
      (node (ref "R9") (pin "1") (pinfunction "1_1") (pintype "passive"))
      (node (ref "SENSOR2") (pin "CAT") (pinfunction "CATH_CAT") (pintype "bidirectional"))
    )
    (net (code "45") (name "Net-(U$3-CAT)") (class "Default")
      (node (ref "R26") (pin "1") (pinfunction "1_1") (pintype "passive"))
      (node (ref "U$3") (pin "CATH") (pinfunction "CAT_CATH") (pintype "bidirectional"))
    )
    (net (code "46") (name "Net-(U$3-EMIT)") (class "Default")
      (node (ref "R28") (pin "1") (pinfunction "1_1") (pintype "passive"))
      (node (ref "U$3") (pin "GND") (pinfunction "EMIT_GND") (pintype "bidirectional"))
    )
    (net (code "47") (name "Net-(U$4-CAT)") (class "Default")
      (node (ref "R27") (pin "1") (pinfunction "1_1") (pintype "passive"))
      (node (ref "U$4") (pin "CATH") (pinfunction "CAT_CATH") (pintype "bidirectional"))
    )
    (net (code "48") (name "Net-(U$4-EMIT)") (class "Default")
      (node (ref "R29") (pin "1") (pinfunction "1_1") (pintype "passive"))
      (node (ref "U$4") (pin "GND") (pinfunction "EMIT_GND") (pintype "bidirectional"))
    )
    (net (code "49") (name "Net-(U1-PB1)") (class "Default")
      (node (ref "U$7") (pin "POS") (pinfunction "POS_POS") (pintype "bidirectional"))
      (node (ref "U1") (pin "15") (pinfunction "PB1_15") (pintype "bidirectional"))
    )
    (net (code "50") (name "Net-(U1-PF0-OSC_IN)") (class "Default")
      (node (ref "C3") (pin "1") (pinfunction "1_1") (pintype "passive"))
      (node (ref "U1") (pin "2") (pinfunction "PF0-OSC_IN_2") (pintype "bidirectional"))
      (node (ref "Y1") (pin "IN/OUT") (pinfunction "IN/OUT_IN/OUT") (pintype "passive"))
    )
    (net (code "51") (name "Net-(U10-EN)") (class "Default")
      (node (ref "R1") (pin "1") (pinfunction "1_1") (pintype "passive"))
      (node (ref "R6") (pin "2") (pinfunction "2_2") (pintype "passive"))
      (node (ref "TP29") (pin "1") (pinfunction "1_1") (pintype "passive"))
      (node (ref "U10") (pin "1") (pinfunction "PS/SYNC_1") (pintype "input"))
      (node (ref "U10") (pin "14") (pinfunction "EN_14") (pintype "input"))
    )
    (net (code "52") (name "Net-(U10-FB)") (class "Default")
      (node (ref "R2") (pin "1") (pinfunction "1_1") (pintype "passive"))
      (node (ref "R3") (pin "2") (pinfunction "2_2") (pintype "passive"))
      (node (ref "U10") (pin "5") (pinfunction "FB_5") (pintype "passive"))
    )
    (net (code "53") (name "Net-(U10-FB2)") (class "Default")
      (node (ref "TP27") (pin "1") (pinfunction "1_1") (pintype "passive"))
      (node (ref "U10") (pin "6") (pinfunction "FB2_6") (pintype "passive"))
    )
    (net (code "54") (name "Net-(U10-L1)") (class "Default")
      (node (ref "L1") (pin "1") (pinfunction "1_1") (pintype "passive"))
      (node (ref "U10") (pin "11") (pinfunction "L1_11") (pintype "passive"))
    )
    (net (code "55") (name "Net-(U10-L2)") (class "Default")
      (node (ref "L1") (pin "2") (pinfunction "2_2") (pintype "passive"))
      (node (ref "U10") (pin "9") (pinfunction "L2_9") (pintype "passive"))
    )
    (net (code "56") (name "Net-(U10-PG)") (class "Default")
      (node (ref "R5") (pin "1") (pinfunction "1_1") (pintype "passive"))
      (node (ref "TP26") (pin "1") (pinfunction "1_1") (pintype "passive"))
      (node (ref "U10") (pin "2") (pinfunction "PG_2") (pintype "open_collector"))
    )
    (net (code "57") (name "Net-(U10-VAUX)") (class "Default")
      (node (ref "C7") (pin "1") (pinfunction "1_1") (pintype "passive"))
      (node (ref "U10") (pin "3") (pinfunction "VAUX_3") (pintype "output"))
    )
    (net (code "58") (name "Net-(U10-VSEL)") (class "Default")
      (node (ref "R4") (pin "2") (pinfunction "2_2") (pintype "passive"))
      (node (ref "TP28") (pin "1") (pinfunction "1_1") (pintype "passive"))
      (node (ref "U10") (pin "15") (pinfunction "VSEL_15") (pintype "input"))
    )
    (net (code "59") (name "OSC_OUT") (class "Default")
      (node (ref "C4") (pin "1") (pinfunction "1_1") (pintype "passive"))
      (node (ref "U1") (pin "3") (pinfunction "PF1-OSC_OUT_3") (pintype "bidirectional"))
      (node (ref "Y1") (pin "OUT/IN") (pinfunction "OUT/IN_OUT/IN") (pintype "passive"))
    )
    (net (code "60") (name "POT_OUT_AN") (class "Default")
      (node (ref "LA") (pin "4") (pinfunction "4_4") (pintype "passive"))
      (node (ref "U1") (pin "20") (pinfunction "PA10_20") (pintype "bidirectional"))
    )
    (net (code "61") (name "PULSEOUT") (class "Default")
      (node (ref "DCMOTOR") (pin "5") (pinfunction "5_5") (pintype "passive"))
      (node (ref "R13") (pin "1") (pinfunction "1_1") (pintype "passive"))
    )
    (net (code "62") (name "SENSOR1") (class "Default")
      (node (ref "R7") (pin "2") (pinfunction "2_2") (pintype "passive"))
      (node (ref "SENSOR") (pin "EMIT") (pinfunction "EMIT_EMIT") (pintype "bidirectional"))
      (node (ref "U1") (pin "9") (pinfunction "PA3_9") (pintype "bidirectional"))
    )
    (net (code "63") (name "SENSOR2") (class "Default")
      (node (ref "R10") (pin "2") (pinfunction "2_2") (pintype "passive"))
      (node (ref "SENSOR2") (pin "EMIT") (pinfunction "EMIT_EMIT") (pintype "bidirectional"))
      (node (ref "U1") (pin "10") (pinfunction "PA4_10") (pintype "bidirectional"))
    )
    (net (code "64") (name "SENSOR_ON") (class "Default")
      (node (ref "R36") (pin "1") (pinfunction "1_1") (pintype "passive"))
      (node (ref "U$2") (pin "1") (pinfunction "G_1") (pintype "passive"))
      (node (ref "U1") (pin "27") (pinfunction "PB4_27") (pintype "bidirectional"))
    )
    (net (code "65") (name "SWCLK") (class "Default")
      (node (ref "CM1") (pin "4") (pinfunction "SWDCLK/TCK_4") (pintype "passive"))
      (node (ref "U1") (pin "24") (pinfunction "PA14-SWCLK_24") (pintype "bidirectional"))
    )
    (net (code "66") (name "SWDIO") (class "Default")
      (node (ref "CM1") (pin "2") (pinfunction "SWDIO/TMS_2") (pintype "passive"))
      (node (ref "U1") (pin "23") (pinfunction "PA13-SWDIO_23") (pintype "bidirectional"))
    )
    (net (code "67") (name "T_GND") (class "Default")
      (node (ref "JP2") (pin "5") (pinfunction "5_5") (pintype "passive"))
      (node (ref "R26") (pin "2") (pinfunction "2_2") (pintype "passive"))
      (node (ref "R27") (pin "2") (pinfunction "2_2") (pintype "passive"))
    )
    (net (code "68") (name "USART2_RX") (class "Default")
      (node (ref "U1") (pin "25") (pinfunction "PA15_25") (pintype "bidirectional"))
    )
    (net (code "69") (name "USART2_TX") (class "Default")
      (node (ref "U1") (pin "8") (pinfunction "PA2_8") (pintype "bidirectional"))
    )
    (net (code "70") (name "VUMB") (class "Default")
      (node (ref "C11") (pin "1") (pinfunction "1_1") (pintype "passive"))
      (node (ref "D1") (pin "1") (pinfunction "+_1") (pintype "passive"))
      (node (ref "JP2") (pin "1") (pinfunction "1_1") (pintype "passive"))
      (node (ref "U$5") (pin "VCC") (pinfunction "VCC_VCC") (pintype "bidirectional"))
    )
    (net (code "71") (name "unconnected-(CM1-NC{slash}TDI-Pad8)") (class "Default")
      (node (ref "CM1") (pin "8") (pinfunction "NC/TDI_8") (pintype "passive"))
    )
    (net (code "72") (name "unconnected-(CM1-SWO{slash}TDO-Pad6)") (class "Default")
      (node (ref "CM1") (pin "6") (pinfunction "SWO/TDO_6") (pintype "passive"))
    )
    (net (code "73") (name "unconnected-(IC1-EP-Pad9)") (class "Default")
      (node (ref "IC1") (pin "9") (pinfunction "EP_9") (pintype "bidirectional"))
    )
    (net (code "74") (name "unconnected-(U1-PB6-Pad29)") (class "Default")
      (node (ref "U1") (pin "29") (pinfunction "PB6_29") (pintype "bidirectional"))
    )
    (net (code "75") (name "unconnected-(U1-PB8-BOOT0-Pad31)") (class "Default")
      (node (ref "U1") (pin "31") (pinfunction "PB8-BOOT0_31") (pintype "bidirectional"))
    )
  )
)
